# LINK2_LPC4322-USB-BRPWR.net
KiCad netlist of a schematic drawn in Altium Designer
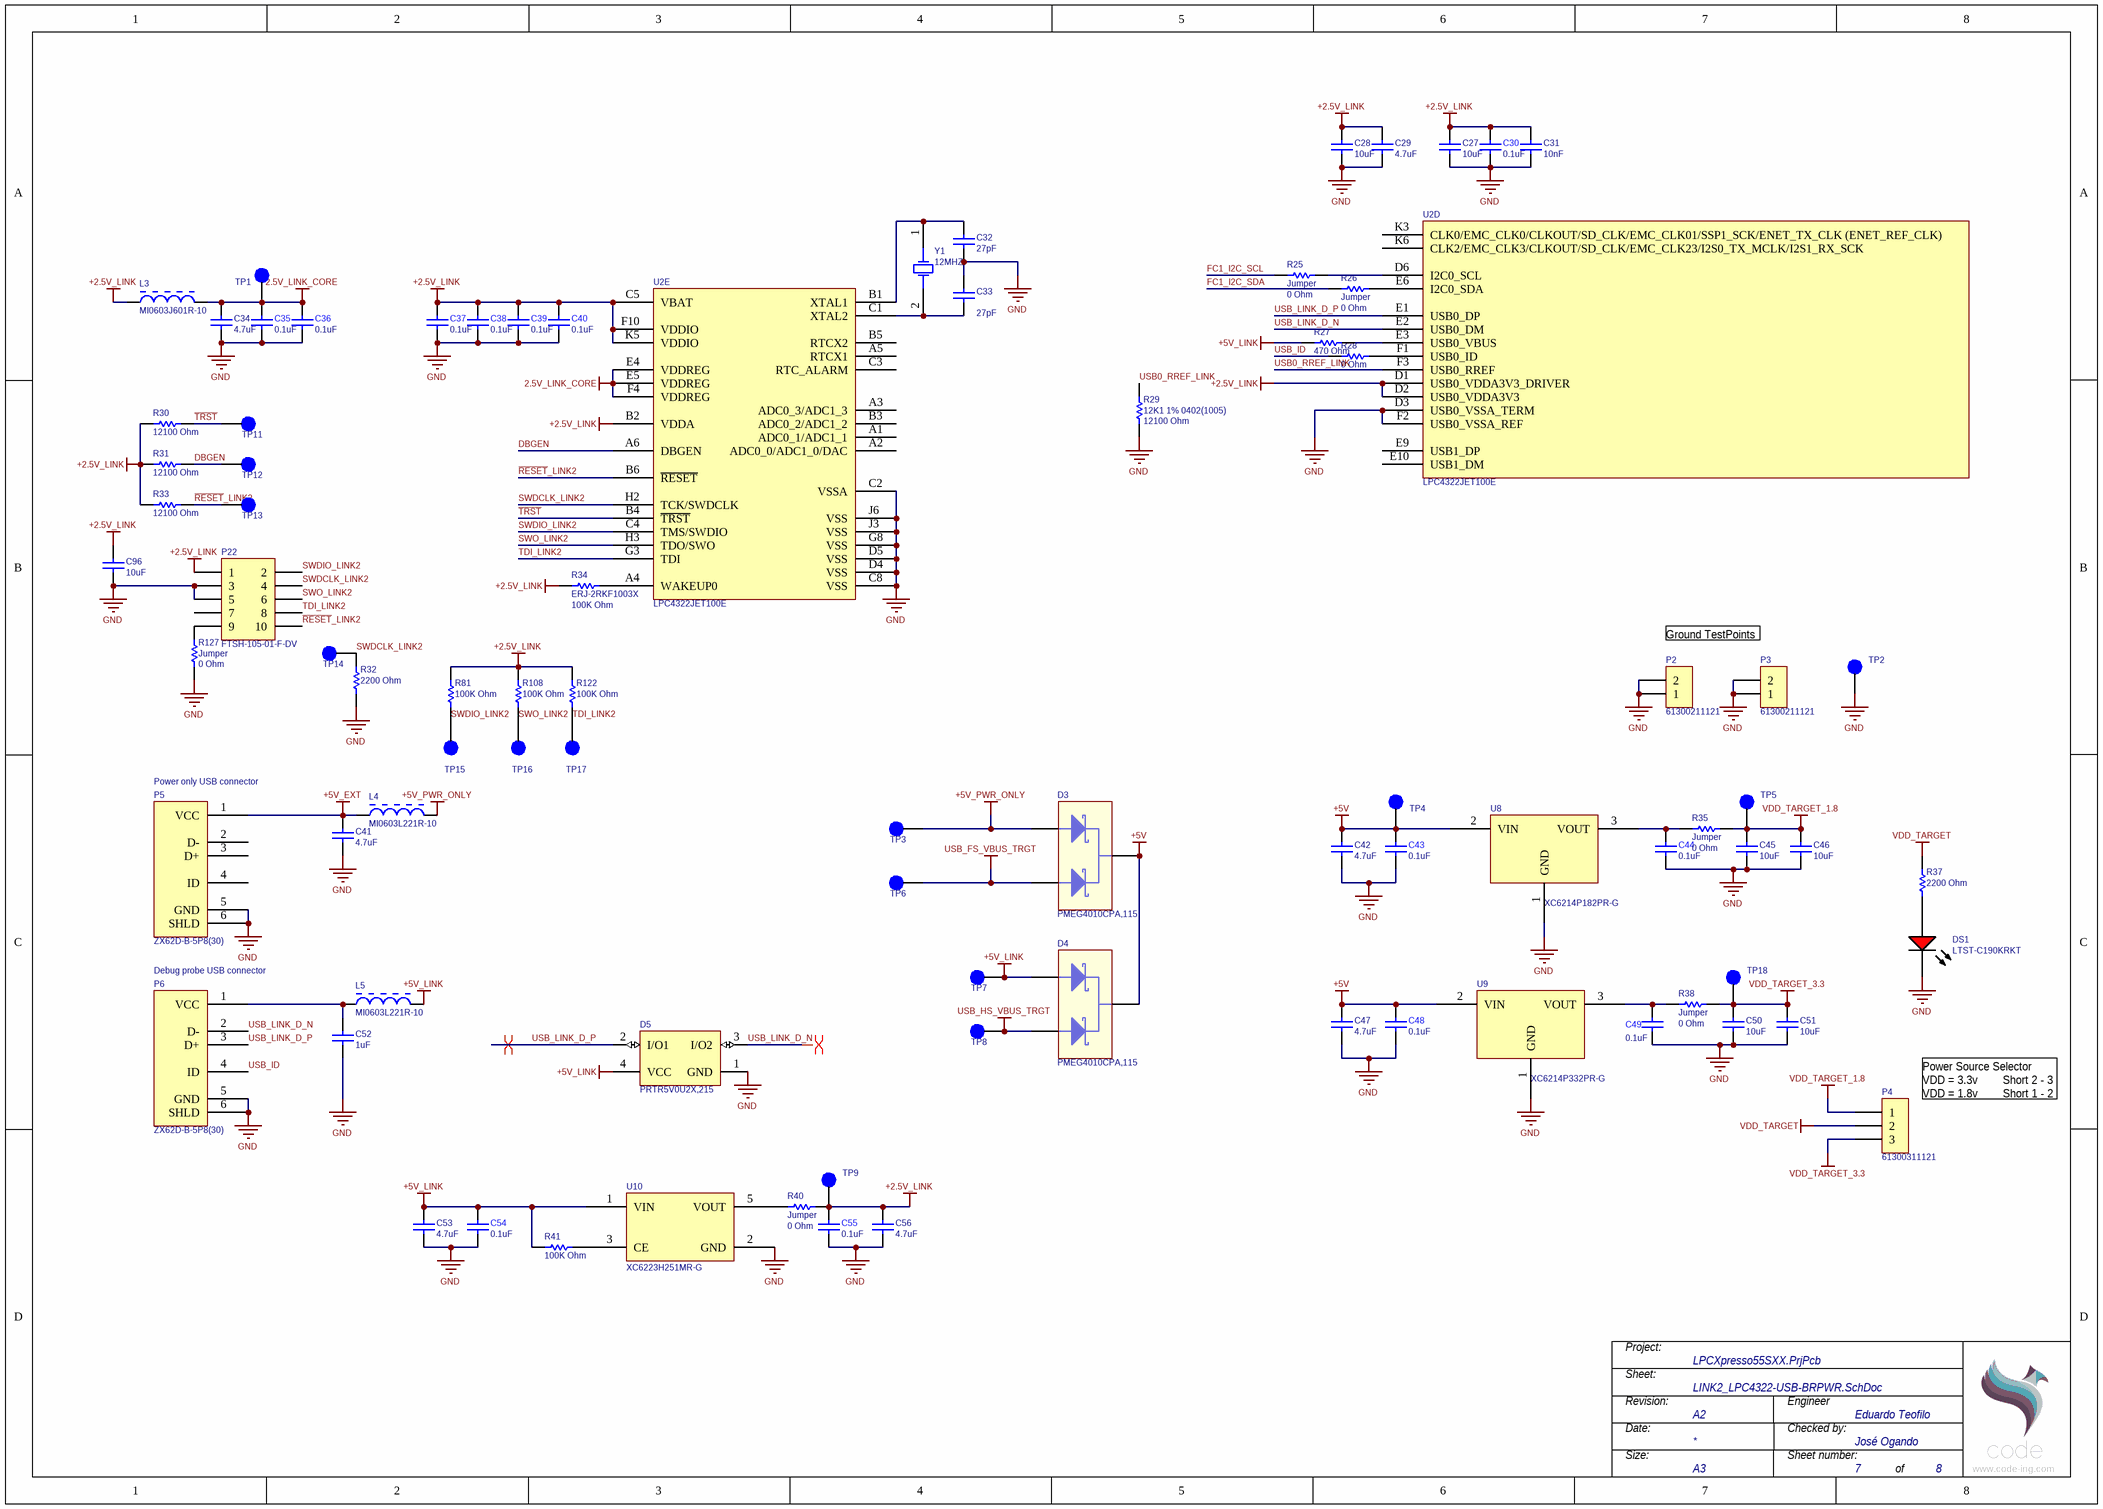
[diagram p0: LINK2_LPC4322-USB-BRPWR.SchDoc]

(export (version "E")
  (design (tool "Eeschema 10.0.6"))
  (components
    (comp (ref "C27")
      (value "10uF")
      (footprint "CAPC0805(2012)145_L")
      (description "CAP 10uF 10V ±10% 0805 (2012 Metric) Thickness 1.45mm SMD")
      (fields (field (name "TOLERANCE") "Â±10%") (field (name "Comment") "CAP 10uF 10V 0805(2012)"))
      (libsource (lib "Altium Content Vault") (part "CMP-1036-04922-1"))
    )
    (comp (ref "C28")
      (value "10uF")
      (footprint "CAPC0805(2012)145_L")
      (description "CAP 10uF 10V ±10% 0805 (2012 Metric) Thickness 1.45mm SMD")
      (fields (field (name "TOLERANCE") "Â±10%") (field (name "Comment") "CAP 10uF 10V 0805(2012)"))
      (libsource (lib "Altium Content Vault") (part "CMP-1036-04922-1"))
    )
    (comp (ref "C29")
      (value "4.7uF")
      (footprint "CAPC0603(1608)100_L")
      (description "CAP 4.7uF 10V ±10% 0603 (1608 Metric) Thickness 1mm SMD")
      (fields (field (name "TOLERANCE") "Â±10%") (field (name "Comment") "CAP 4.7uF 10V 0603(1608)"))
      (libsource (lib "Altium Content Vault") (part "CMP-1035-02785-1"))
    )
    (comp (ref "C30")
      (value "0.1uF")
      (footprint "CAPC1005")
      (description "Capacitor, Yageo, Ceramic, 0.1uF 10% 16V 0402 (1005) X7R")
      (fields
        (field (name "TOLERANCE") "10 %")
        (field (name "Comment") "CC0402KRX7R7BB104")
        (field (name "PUBLISHER") "Altium")
      )
      (libsource (lib "Altium Content Vault") (part "CMP-0001-00074-1"))
    )
    (comp (ref "C31")
      (value "10nF")
      (footprint "CAPC0402(1005)60_L")
      (description "CAP 10nF 25V ±10% 0402 (1005 Metric) Thickness 0.6mm SMD")
      (fields (field (name "TOLERANCE") "Â±10%") (field (name "Comment") "CAP 10nF 25V 0402(1005)"))
      (libsource (lib "Altium Content Vault") (part "CMP-1034-01880-1"))
    )
    (comp (ref "C32")
      (value "27pF")
      (footprint "CAPC0402(1005)60_L")
      (description "CAP 27pF 50V ±5% 0402 (1005 Metric) Thickness 0.6mm SMD")
      (fields (field (name "TOLERANCE") "Â±5%") (field (name "Comment") "CAP 27pF 50V 0402(1005)"))
      (libsource (lib "Altium Content Vault") (part "CMP-1034-00963-1"))
    )
    (comp (ref "C33")
      (value "27pF")
      (footprint "CAPC0402(1005)60_L")
      (description "CAP 27pF 50V ±5% 0402 (1005 Metric) Thickness 0.6mm SMD")
      (fields (field (name "TOLERANCE") "Â±5%") (field (name "Comment") "CAP 27pF 50V 0402(1005)"))
      (libsource (lib "Altium Content Vault") (part "CMP-1034-00963-1"))
    )
    (comp (ref "C34")
      (value "4.7uF")
      (footprint "CAPC0603(1608)100_L")
      (description "CAP 4.7uF 10V ±10% 0603 (1608 Metric) Thickness 1mm SMD")
      (fields (field (name "TOLERANCE") "Â±10%") (field (name "Comment") "CAP 4.7uF 10V 0603(1608)"))
      (libsource (lib "Altium Content Vault") (part "CMP-1035-02785-1"))
    )
    (comp (ref "C35")
      (value "0.1uF")
      (footprint "CAPC1005")
      (description "Capacitor, Yageo, Ceramic, 0.1uF 10% 16V 0402 (1005) X7R")
      (fields
        (field (name "TOLERANCE") "10 %")
        (field (name "Comment") "CC0402KRX7R7BB104")
        (field (name "PUBLISHER") "Altium")
      )
      (libsource (lib "Altium Content Vault") (part "CMP-0001-00074-1"))
    )
    (comp (ref "C36")
      (value "0.1uF")
      (footprint "CAPC1005")
      (description "Capacitor, Yageo, Ceramic, 0.1uF 10% 16V 0402 (1005) X7R")
      (fields
        (field (name "TOLERANCE") "10 %")
        (field (name "Comment") "CC0402KRX7R7BB104")
        (field (name "PUBLISHER") "Altium")
      )
      (libsource (lib "Altium Content Vault") (part "CMP-0001-00074-1"))
    )
    (comp (ref "C37")
      (value "0.1uF")
      (footprint "CAPC1005")
      (description "Capacitor, Yageo, Ceramic, 0.1uF 10% 16V 0402 (1005) X7R")
      (fields
        (field (name "TOLERANCE") "10 %")
        (field (name "Comment") "CC0402KRX7R7BB104")
        (field (name "PUBLISHER") "Altium")
      )
      (libsource (lib "Altium Content Vault") (part "CMP-0001-00074-1"))
    )
    (comp (ref "C38")
      (value "0.1uF")
      (footprint "CAPC1005")
      (description "Capacitor, Yageo, Ceramic, 0.1uF 10% 16V 0402 (1005) X7R")
      (fields
        (field (name "TOLERANCE") "10 %")
        (field (name "Comment") "CC0402KRX7R7BB104")
        (field (name "PUBLISHER") "Altium")
      )
      (libsource (lib "Altium Content Vault") (part "CMP-0001-00074-1"))
    )
    (comp (ref "C39")
      (value "0.1uF")
      (footprint "CAPC1005")
      (description "Capacitor, Yageo, Ceramic, 0.1uF 10% 16V 0402 (1005) X7R")
      (fields
        (field (name "TOLERANCE") "10 %")
        (field (name "Comment") "CC0402KRX7R7BB104")
        (field (name "PUBLISHER") "Altium")
      )
      (libsource (lib "Altium Content Vault") (part "CMP-0001-00074-1"))
    )
    (comp (ref "C40")
      (value "0.1uF")
      (footprint "CAPC1005")
      (description "Capacitor, Yageo, Ceramic, 0.1uF 10% 16V 0402 (1005) X7R")
      (fields
        (field (name "TOLERANCE") "10 %")
        (field (name "Comment") "CC0402KRX7R7BB104")
        (field (name "PUBLISHER") "Altium")
      )
      (libsource (lib "Altium Content Vault") (part "CMP-0001-00074-1"))
    )
    (comp (ref "C41")
      (value "4.7uF")
      (footprint "CAPC0603(1608)100_L")
      (description "CAP 4.7uF 10V ±10% 0603 (1608 Metric) Thickness 1mm SMD")
      (fields (field (name "TOLERANCE") "Â±10%") (field (name "Comment") "CAP 4.7uF 10V 0603(1608)"))
      (libsource (lib "Altium Content Vault") (part "CMP-1035-02785-1"))
    )
    (comp (ref "C42")
      (value "4.7uF")
      (footprint "CAPC0603(1608)100_L")
      (description "CAP 4.7uF 10V ±10% 0603 (1608 Metric) Thickness 1mm SMD")
      (fields (field (name "TOLERANCE") "Â±10%") (field (name "Comment") "CAP 4.7uF 10V 0603(1608)"))
      (libsource (lib "Altium Content Vault") (part "CMP-1035-02785-1"))
    )
    (comp (ref "C43")
      (value "0.1uF")
      (footprint "CAPC1005")
      (description "Capacitor, Yageo, Ceramic, 0.1uF 10% 16V 0402 (1005) X7R")
      (fields
        (field (name "TOLERANCE") "10 %")
        (field (name "Comment") "CC0402KRX7R7BB104")
        (field (name "PUBLISHER") "Altium")
      )
      (libsource (lib "Altium Content Vault") (part "CMP-0001-00074-1"))
    )
    (comp (ref "C44")
      (value "0.1uF")
      (footprint "CAPC1005")
      (description "Capacitor, Yageo, Ceramic, 0.1uF 10% 16V 0402 (1005) X7R")
      (fields
        (field (name "TOLERANCE") "10 %")
        (field (name "Comment") "CC0402KRX7R7BB104")
        (field (name "PUBLISHER") "Altium")
      )
      (libsource (lib "Altium Content Vault") (part "CMP-0001-00074-1"))
    )
    (comp (ref "C45")
      (value "10uF")
      (footprint "CAPC0805(2012)145_L")
      (description "CAP 10uF 10V ±10% 0805 (2012 Metric) Thickness 1.45mm SMD")
      (fields (field (name "TOLERANCE") "Â±10%") (field (name "Comment") "CAP 10uF 10V 0805(2012)"))
      (libsource (lib "Altium Content Vault") (part "CMP-1036-04922-1"))
    )
    (comp (ref "C46")
      (value "10uF")
      (footprint "CAPC0805(2012)145_L")
      (description "CAP 10uF 10V ±10% 0805 (2012 Metric) Thickness 1.45mm SMD")
      (fields (field (name "TOLERANCE") "Â±10%") (field (name "Comment") "CAP 10uF 10V 0805(2012)"))
      (libsource (lib "Altium Content Vault") (part "CMP-1036-04922-1"))
    )
    (comp (ref "C47")
      (value "4.7uF")
      (footprint "CAPC0603(1608)100_L")
      (description "CAP 4.7uF 10V ±10% 0603 (1608 Metric) Thickness 1mm SMD")
      (fields (field (name "TOLERANCE") "Â±10%") (field (name "Comment") "CAP 4.7uF 10V 0603(1608)"))
      (libsource (lib "Altium Content Vault") (part "CMP-1035-02785-1"))
    )
    (comp (ref "C48")
      (value "0.1uF")
      (footprint "CAPC1005")
      (description "Capacitor, Yageo, Ceramic, 0.1uF 10% 16V 0402 (1005) X7R")
      (fields
        (field (name "TOLERANCE") "10 %")
        (field (name "Comment") "CC0402KRX7R7BB104")
        (field (name "PUBLISHER") "Altium")
      )
      (libsource (lib "Altium Content Vault") (part "CMP-0001-00074-1"))
    )
    (comp (ref "C49")
      (value "0.1uF")
      (footprint "CAPC1005")
      (description "Capacitor, Yageo, Ceramic, 0.1uF 10% 16V 0402 (1005) X7R")
      (fields
        (field (name "TOLERANCE") "10 %")
        (field (name "Comment") "CC0402KRX7R7BB104")
        (field (name "PUBLISHER") "Altium")
      )
      (libsource (lib "Altium Content Vault") (part "CMP-0001-00074-1"))
    )
    (comp (ref "C50")
      (value "10uF")
      (footprint "CAPC0805(2012)145_L")
      (description "CAP 10uF 10V ±10% 0805 (2012 Metric) Thickness 1.45mm SMD")
      (fields (field (name "TOLERANCE") "Â±10%") (field (name "Comment") "CAP 10uF 10V 0805(2012)"))
      (libsource (lib "Altium Content Vault") (part "CMP-1036-04922-1"))
    )
    (comp (ref "C51")
      (value "10uF")
      (footprint "CAPC0805(2012)145_L")
      (description "CAP 10uF 10V ±10% 0805 (2012 Metric) Thickness 1.45mm SMD")
      (fields (field (name "TOLERANCE") "Â±10%") (field (name "Comment") "CAP 10uF 10V 0805(2012)"))
      (libsource (lib "Altium Content Vault") (part "CMP-1036-04922-1"))
    )
    (comp (ref "C52")
      (value "1uF")
      (footprint "CAPC0402(1005)60_L")
      (description "CAP 1uF 10V -20% to +80% 0402 (1005 Metric) Thickness 0.6mm SMD")
      (fields (field (name "TOLERANCE") "-20% to +80%") (field (name "Comment") "CAP 1uF 10V 0402(1005)"))
      (libsource (lib "Altium Content Vault") (part "CMP-1034-02118-1"))
    )
    (comp (ref "C53")
      (value "4.7uF")
      (footprint "CAPC0603(1608)100_L")
      (description "CAP 4.7uF 10V ±10% 0603 (1608 Metric) Thickness 1mm SMD")
      (fields (field (name "TOLERANCE") "Â±10%") (field (name "Comment") "CAP 4.7uF 10V 0603(1608)"))
      (libsource (lib "Altium Content Vault") (part "CMP-1035-02785-1"))
    )
    (comp (ref "C54")
      (value "0.1uF")
      (footprint "CAPC1005")
      (description "Capacitor, Yageo, Ceramic, 0.1uF 10% 16V 0402 (1005) X7R")
      (fields
        (field (name "TOLERANCE") "10 %")
        (field (name "Comment") "CC0402KRX7R7BB104")
        (field (name "PUBLISHER") "Altium")
      )
      (libsource (lib "Altium Content Vault") (part "CMP-0001-00074-1"))
    )
    (comp (ref "C55")
      (value "0.1uF")
      (footprint "CAPC1005")
      (description "Capacitor, Yageo, Ceramic, 0.1uF 10% 16V 0402 (1005) X7R")
      (fields
        (field (name "TOLERANCE") "10 %")
        (field (name "Comment") "CC0402KRX7R7BB104")
        (field (name "PUBLISHER") "Altium")
      )
      (libsource (lib "Altium Content Vault") (part "CMP-0001-00074-1"))
    )
    (comp (ref "C56")
      (value "4.7uF")
      (footprint "CAPC0603(1608)100_L")
      (description "CAP 4.7uF 10V ±10% 0603 (1608 Metric) Thickness 1mm SMD")
      (fields (field (name "TOLERANCE") "Â±10%") (field (name "Comment") "CAP 4.7uF 10V 0603(1608)"))
      (libsource (lib "Altium Content Vault") (part "CMP-1035-02785-1"))
    )
    (comp (ref "C96")
      (value "10uF")
      (footprint "CAPC0805(2012)145_L")
      (description "CAP 10uF 10V ±10% 0805 (2012 Metric) Thickness 1.45mm SMD")
      (fields (field (name "TOLERANCE") "Â±10%") (field (name "Comment") "CAP 10uF 10V 0805(2012)"))
      (libsource (lib "Altium Content Vault") (part "CMP-1036-04922-1"))
    )
    (comp (ref "D3")
      (value "PMEG4010CPA,115")
      (footprint "SOT1061")
      (description "DIODE ARRAY SCHOTTKY 40V 3HUSON")
      (fields
        (field (name "MANUFACTURER") "Nexperia USA Inc.")
        (field (name "CREATED BY") "eteoflo")
        (field (name "MODIFIED BY") "*")
      )
      (libsource (lib "Diodes, Rectifiers - Arrays") (part "PMEG4010CPA,115"))
    )
    (comp (ref "D4")
      (value "PMEG4010CPA,115")
      (footprint "SOT1061")
      (description "DIODE ARRAY SCHOTTKY 40V 3HUSON")
      (fields
        (field (name "MANUFACTURER") "Nexperia USA Inc.")
        (field (name "CREATED BY") "eteoflo")
        (field (name "MODIFIED BY") "*")
      )
      (libsource (lib "Diodes, Rectifiers - Arrays") (part "PMEG4010CPA,115"))
    )
    (comp (ref "D5")
      (value "PRTR5V0U2X,215")
      (footprint "NXP-SOT143B-4_V")
      (fields (field (name "MANUFACTURER") "NXP Semiconductors"))
      (libsource (lib "Altium Content Vault") (part "NXP-PRTR5V0U2X,215-4"))
    )
    (comp (ref "DS1")
      (value "LTST-C190KRKT")
      (footprint "LTST-C191KRKT_V")
      (description "LED Uni-Color Red, 62.5 mW, 5 V, -30 to 85 degC, 2-Pin SMD, RoHS, Tape and Reel")
      (fields (field (name "TOLERANCE") "20%"))
      (libsource (lib "Altium Content Vault") (part "LED-RED-AK-2"))
    )
    (comp (ref "L3")
      (value "MI0603J601R-10")
      (footprint "LIRD-MI0603J601R-10_V")
      (description "Ferrite Bead, 600 Ohm, 1 A, -40 to 125 degC, 2-Pin SMD, RoHS, Tape and Reel")
      (fields (field (name "MANUFACTURER") "Laird"))
      (libsource (lib "Altium Content Vault") (part "IND-FB-2"))
    )
    (comp (ref "L4")
      (value "MI0603L221R-10")
      (footprint "LIRD-HZ0603C601R-10-2_V")
      (description "Chip Bead, 100 MHz, 2 A, -40 to 125 degC, 2-Pin SMD (0603), RoHS, Tape and Reel")
      (fields (field (name "MANUFACTURER") "LairdTechnologies"))
      (libsource (lib "Altium Content Vault") (part "IND-FB-2"))
    )
    (comp (ref "L5")
      (value "MI0603L221R-10")
      (footprint "LIRD-HZ0603C601R-10-2_V")
      (description "Chip Bead, 100 MHz, 2 A, -40 to 125 degC, 2-Pin SMD (0603), RoHS, Tape and Reel")
      (fields (field (name "MANUFACTURER") "LairdTechnologies"))
      (libsource (lib "Altium Content Vault") (part "IND-FB-2"))
    )
    (comp (ref "P2")
      (value "61300211121")
      (footprint "61300211121")
      (description "HEADER 2POS SNGL T/H 2.54MM")
      (fields
        (field (name "MANUFACTURER") "Wurth Electronics Inc")
        (field (name "MODIFIED BY") "*")
        (field (name "CREATED BY") "gmoreno")
      )
      (libsource (lib "Rectangular - Headers, Male Pins") (part "61300211121"))
    )
    (comp (ref "P3")
      (value "61300211121")
      (footprint "61300211121")
      (description "HEADER 2POS SNGL T/H 2.54MM")
      (fields
        (field (name "MANUFACTURER") "Wurth Electronics Inc")
        (field (name "MODIFIED BY") "*")
        (field (name "CREATED BY") "gmoreno")
      )
      (libsource (lib "Rectangular - Headers, Male Pins") (part "61300211121"))
    )
    (comp (ref "P4")
      (value "61300311121")
      (footprint "61300311121")
      (description "HEADER 3POS SNGL T/H 2.54MM")
      (fields
        (field (name "MANUFACTURER") "Wurth Electronics Inc")
        (field (name "MODIFIED BY") "*")
        (field (name "CREATED BY") "gmoreno")
      )
      (libsource (lib "Rectangular - Headers, Male Pins") (part "61300311121"))
    )
    (comp (ref "P5")
      (value "ZX62D-B-5P8(30)")
      (footprint "ZX62D-B-5P8(30)")
      (description "CONN RCPT USB MICRO B SMD")
      (fields
        (field (name "MANUFACTURER") "Hirose Electric Co Ltd")
        (field (name "CREATED BY") "eteofilo")
        (field (name "MODIFIED BY") "*")
      )
      (libsource (lib "USB, DVI, HDMI Connectors") (part "ZX62D-B-5P8(30)"))
    )
    (comp (ref "P6")
      (value "ZX62D-B-5P8(30)")
      (footprint "ZX62D-B-5P8(30)")
      (description "CONN RCPT USB MICRO B SMD")
      (fields
        (field (name "MANUFACTURER") "Hirose Electric Co Ltd")
        (field (name "CREATED BY") "eteofilo")
        (field (name "MODIFIED BY") "*")
      )
      (libsource (lib "USB, DVI, HDMI Connectors") (part "ZX62D-B-5P8(30)"))
    )
    (comp (ref "P22")
      (value "FTSH-105-01-F-DV")
      (footprint "FTSH-105-01-L-DV-K")
      (description "CONN HEADER 10POS DUAL .05\" SMD")
      (fields
        (field (name "MANUFACTURER") "Samtec Inc")
        (field (name "CREATED BY") "gmoreno")
        (field (name "MODIFIED BY") "*")
      )
      (libsource (lib "Rectangular - Headers, Male Pins") (part "FTSH-105-01-F-DV"))
    )
    (comp (ref "R25")
      (value "Jumper")
      (footprint "RESC0402(1005)_L")
      (description "Jumper 0402 (1005 Metric)")
      (fields (field (name "TOLERANCE") "None") (field (name "ALTIUM_VALUE") "0 Ohm"))
      (libsource (lib "Altium Content Vault") (part "CMP-1011-00001-1"))
    )
    (comp (ref "R26")
      (value "Jumper")
      (footprint "RESC0402(1005)_L")
      (description "Jumper 0402 (1005 Metric)")
      (fields (field (name "TOLERANCE") "None") (field (name "ALTIUM_VALUE") "0 Ohm"))
      (libsource (lib "Altium Content Vault") (part "CMP-1011-00001-1"))
    )
    (comp (ref "R27")
      (value "470 Ohm")
      (footprint "RESC0402(1005)_L")
      (description "470R 0.063W 5% 0402 (1005 Metric)  SMD")
      (fields (field (name "TOLERANCE") "5 %") (field (name "POWER") "0.063 W"))
      (libsource (lib "Altium Content Vault") (part "CMP-1011-00066-1"))
    )
    (comp (ref "R28")
      (value "0 Ohm")
      (footprint "RESC0402(1005)_L")
      (description "Jumper 0402 (1005 Metric)")
      (fields (field (name "TOLERANCE") "None") (field (name "Comment") "Jumper 0402(1005)"))
      (libsource (lib "Altium Content Vault") (part "CMP-1011-00001-1"))
    )
    (comp (ref "R29")
      (value "12K1 1% 0402(1005)")
      (footprint "RESC0402(1005)_L")
      (description "12K1 0.063W 1% 0402 (1005 Metric)  SMD")
      (fields
        (field (name "ALTIUM_VALUE") "12100 Ohm")
        (field (name "POWER") "0.063 W")
        (field (name "TOLERANCE") "1 %")
      )
      (libsource (lib "Altium Content Vault") (part "CMP-1011-00632-1"))
    )
    (comp (ref "R30")
      (value "12100 Ohm")
      (footprint "RESC0402(1005)_L")
      (description "12K1 0.063W 1% 0402 (1005 Metric)  SMD")
      (fields (field (name "POWER") "0.063 W") (field (name "TOLERANCE") "1 %"))
      (libsource (lib "Altium Content Vault") (part "CMP-1011-00632-1"))
    )
    (comp (ref "R31")
      (value "12100 Ohm")
      (footprint "RESC0402(1005)_L")
      (description "12K1 0.063W 1% 0402 (1005 Metric)  SMD")
      (fields (field (name "POWER") "0.063 W") (field (name "TOLERANCE") "1 %"))
      (libsource (lib "Altium Content Vault") (part "CMP-1011-00632-1"))
    )
    (comp (ref "R32")
      (value "2200 Ohm")
      (footprint "RESC0402(1005)_L")
      (description "2K2 0.063W 1% 0402 (1005 Metric)  SMD")
      (fields (field (name "POWER") "0.063 W") (field (name "TOLERANCE") "1 %"))
      (libsource (lib "Altium Content Vault") (part "CMP-1011-00546-1"))
    )
    (comp (ref "R33")
      (value "12100 Ohm")
      (footprint "RESC0402(1005)_L")
      (description "12K1 0.063W 1% 0402 (1005 Metric)  SMD")
      (fields (field (name "POWER") "0.063 W") (field (name "TOLERANCE") "1 %"))
      (libsource (lib "Altium Content Vault") (part "CMP-1011-00632-1"))
    )
    (comp (ref "R34")
      (value "ERJ-2RKF1003X")
      (footprint "RESC1005X40X25LL05T05")
      (description "Chip Resistor, 100 KOhm, +/- 1%, 100 mW, -55 to 155 degC, 0402 (1005 Metric), RoHS, Tape and Reel")
      (fields
        (field (name "TOLERANCE") "1%")
        (field (name "MANUFACTURER") "Basic Passives")
        (field (name "ALTIUM_VALUE") "100K Ohm")
      )
      (libsource (lib "Altium Content Vault") (part "RES-2"))
    )
    (comp (ref "R35")
      (value "Jumper")
      (footprint "RESC0402(1005)_L")
      (description "Jumper 0402 (1005 Metric)")
      (fields (field (name "TOLERANCE") "None") (field (name "ALTIUM_VALUE") "0 Ohm"))
      (libsource (lib "Altium Content Vault") (part "CMP-1011-00001-1"))
    )
    (comp (ref "R37")
      (value "2200 Ohm")
      (footprint "RESC0402(1005)_L")
      (description "2K2 0.063W 1% 0402 (1005 Metric)  SMD")
      (fields (field (name "POWER") "0.063 W") (field (name "TOLERANCE") "1 %"))
      (libsource (lib "Altium Content Vault") (part "CMP-1011-00546-1"))
    )
    (comp (ref "R38")
      (value "Jumper")
      (footprint "RESC0402(1005)_L")
      (description "Jumper 0402 (1005 Metric)")
      (fields (field (name "TOLERANCE") "None") (field (name "ALTIUM_VALUE") "0 Ohm"))
      (libsource (lib "Altium Content Vault") (part "CMP-1011-00001-1"))
    )
    (comp (ref "R40")
      (value "Jumper")
      (footprint "RESC0402(1005)_L")
      (description "Jumper 0402 (1005 Metric)")
      (fields (field (name "TOLERANCE") "None") (field (name "ALTIUM_VALUE") "0 Ohm"))
      (libsource (lib "Altium Content Vault") (part "CMP-1011-00001-1"))
    )
    (comp (ref "R41")
      (value "100K Ohm")
      (footprint "RESC1005X40X25LL05T05")
      (description "Chip Resistor, 100 KOhm, +/- 1%, 100 mW, -55 to 155 degC, 0402 (1005 Metric), RoHS, Tape and Reel")
      (fields (field (name "TOLERANCE") "1%") (field (name "MANUFACTURER") "Basic Passives"))
      (libsource (lib "Altium Content Vault") (part "CMP-2002-00608-3"))
    )
    (comp (ref "R81")
      (value "100K Ohm")
      (footprint "RESC1005X40X25LL05T05")
      (description "Chip Resistor, 100 KOhm, +/- 1%, 100 mW, -55 to 155 degC, 0402 (1005 Metric), RoHS, Tape and Reel")
      (fields (field (name "TOLERANCE") "1%") (field (name "MANUFACTURER") "Basic Passives"))
      (libsource (lib "Altium Content Vault") (part "CMP-2002-00608-3"))
    )
    (comp (ref "R108")
      (value "100K Ohm")
      (footprint "RESC1005X40X25LL05T05")
      (description "Chip Resistor, 100 KOhm, +/- 1%, 100 mW, -55 to 155 degC, 0402 (1005 Metric), RoHS, Tape and Reel")
      (fields (field (name "TOLERANCE") "1%") (field (name "MANUFACTURER") "Basic Passives"))
      (libsource (lib "Altium Content Vault") (part "CMP-2002-00608-3"))
    )
    (comp (ref "R122")
      (value "100K Ohm")
      (footprint "RESC1005X40X25LL05T05")
      (description "Chip Resistor, 100 KOhm, +/- 1%, 100 mW, -55 to 155 degC, 0402 (1005 Metric), RoHS, Tape and Reel")
      (fields (field (name "TOLERANCE") "1%") (field (name "MANUFACTURER") "Basic Passives"))
      (libsource (lib "Altium Content Vault") (part "CMP-2002-00608-3"))
    )
    (comp (ref "R127")
      (value "Jumper")
      (footprint "RESC0402(1005)_L")
      (description "Jumper 0402 (1005 Metric)")
      (fields (field (name "TOLERANCE") "None") (field (name "ALTIUM_VALUE") "0 Ohm"))
      (libsource (lib "Altium Content Vault") (part "CMP-1011-00001-1"))
    )
    (comp (ref "TP1")
      (value "TP 1mm")
      (footprint "SMT Test Point")
      (description "PCB TEST POINT SMT 1mm")
      (fields (field (name "MODIFIED BY") "*") (field (name "CREATED BY") "gmoreno"))
      (libsource (lib "") (part "TP 1mm_1"))
    )
    (comp (ref "TP2")
      (value "TP 1mm")
      (footprint "SMT Test Point")
      (description "PCB TEST POINT SMT 1mm")
      (fields (field (name "MODIFIED BY") "*") (field (name "CREATED BY") "gmoreno"))
      (libsource (lib "") (part "TP 1mm_1"))
    )
    (comp (ref "TP3")
      (value "TP 1mm")
      (footprint "SMT Test Point")
      (description "PCB TEST POINT SMT 1mm")
      (fields (field (name "MODIFIED BY") "*") (field (name "CREATED BY") "gmoreno"))
      (libsource (lib "PCB Test Points") (part "TP 1mm"))
    )
    (comp (ref "TP4")
      (value "TP 1mm")
      (footprint "SMT Test Point")
      (description "PCB TEST POINT SMT 1mm")
      (fields (field (name "MODIFIED BY") "*") (field (name "CREATED BY") "gmoreno"))
      (libsource (lib "") (part "TP 1mm_1"))
    )
    (comp (ref "TP5")
      (value "TP 1mm")
      (footprint "SMT Test Point")
      (description "PCB TEST POINT SMT 1mm")
      (fields (field (name "MODIFIED BY") "*") (field (name "CREATED BY") "gmoreno"))
      (libsource (lib "") (part "TP 1mm_1"))
    )
    (comp (ref "TP6")
      (value "TP 1mm")
      (footprint "SMT Test Point")
      (description "PCB TEST POINT SMT 1mm")
      (fields (field (name "MODIFIED BY") "*") (field (name "CREATED BY") "gmoreno"))
      (libsource (lib "PCB Test Points") (part "TP 1mm"))
    )
    (comp (ref "TP7")
      (value "TP 1mm")
      (footprint "SMT Test Point")
      (description "PCB TEST POINT SMT 1mm")
      (fields (field (name "MODIFIED BY") "*") (field (name "CREATED BY") "gmoreno"))
      (libsource (lib "PCB Test Points") (part "TP 1mm"))
    )
    (comp (ref "TP8")
      (value "TP 1mm")
      (footprint "SMT Test Point")
      (description "PCB TEST POINT SMT 1mm")
      (fields (field (name "MODIFIED BY") "*") (field (name "CREATED BY") "gmoreno"))
      (libsource (lib "PCB Test Points") (part "TP 1mm"))
    )
    (comp (ref "TP9")
      (value "TP 1mm")
      (footprint "SMT Test Point")
      (description "PCB TEST POINT SMT 1mm")
      (fields (field (name "MODIFIED BY") "*") (field (name "CREATED BY") "gmoreno"))
      (libsource (lib "") (part "TP 1mm_1"))
    )
    (comp (ref "TP11")
      (value "TPAD 0.8mm")
      (footprint "TH Test Pad 0.8mm")
      (description "PCB TEST PAD TH 0.8mm")
      (fields (field (name "MODIFIED BY") "*") (field (name "CREATED BY") "eteofilo"))
      (libsource (lib "") (part "TP 0.8mm_1"))
    )
    (comp (ref "TP12")
      (value "TPAD 0.8mm")
      (footprint "TH Test Pad 0.8mm")
      (description "PCB TEST PAD TH 0.8mm")
      (fields (field (name "MODIFIED BY") "*") (field (name "CREATED BY") "eteofilo"))
      (libsource (lib "") (part "TP 0.8mm_1"))
    )
    (comp (ref "TP13")
      (value "TPAD 0.8mm")
      (footprint "TH Test Pad 0.8mm")
      (description "PCB TEST PAD TH 0.8mm")
      (fields (field (name "MODIFIED BY") "*") (field (name "CREATED BY") "eteofilo"))
      (libsource (lib "") (part "TP 0.8mm_1"))
    )
    (comp (ref "TP14")
      (value "TPAD 0.8mm")
      (footprint "TH Test Pad 0.8mm")
      (description "PCB TEST PAD TH 0.8mm")
      (fields (field (name "MODIFIED BY") "*") (field (name "CREATED BY") "eteofilo"))
      (libsource (lib "") (part "TP 0.8mm_2"))
    )
    (comp (ref "TP15")
      (value "TPAD 0.8mm")
      (footprint "TH Test Pad 0.8mm")
      (description "PCB TEST PAD TH 0.8mm")
      (fields (field (name "MODIFIED BY") "*") (field (name "CREATED BY") "eteofilo"))
      (libsource (lib "PCB Test Points") (part "TP 0.8mm"))
    )
    (comp (ref "TP16")
      (value "TPAD 0.8mm")
      (footprint "TH Test Pad 0.8mm")
      (description "PCB TEST PAD TH 0.8mm")
      (fields (field (name "MODIFIED BY") "*") (field (name "CREATED BY") "eteofilo"))
      (libsource (lib "PCB Test Points") (part "TP 0.8mm"))
    )
    (comp (ref "TP17")
      (value "TPAD 0.8mm")
      (footprint "TH Test Pad 0.8mm")
      (description "PCB TEST PAD TH 0.8mm")
      (fields (field (name "MODIFIED BY") "*") (field (name "CREATED BY") "eteofilo"))
      (libsource (lib "PCB Test Points") (part "TP 0.8mm"))
    )
    (comp (ref "TP18")
      (value "TP 1mm")
      (footprint "SMT Test Point")
      (description "PCB TEST POINT SMT 1mm")
      (fields (field (name "MODIFIED BY") "*") (field (name "CREATED BY") "gmoreno"))
      (libsource (lib "") (part "TP 1mm_1"))
    )
    (comp (ref "U2")
      (value "LPC4322JET100E")
      (footprint "BGA100_9x9x1.2mm")
      (description "IC MCU 32BIT 512KB FLASH 100BGA")
      (fields
        (field (name "MANUFACTURER") "NXP")
        (field (name "CREATED BY") "eteofilo")
        (field (name "MODIFIED BY") "*")
      )
      (libsource (lib "Embedded - Microcontrollers") (part "LPC4322JET100E"))
    )
    (comp (ref "U8")
      (value "XC6214P182PR-G")
      (footprint "SOT-89-3")
      (description "IC REG LDO 1.8V 0.5A SOT89-3")
      (fields
        (field (name "MANUFACTURER") "Torex Semiconductor Ltd")
        (field (name "CREATED BY") "eteofilo")
        (field (name "MODIFIED BY") "*")
      )
      (libsource (lib "PMIC - Voltage Regulators - Linear (LDO)") (part "XC6214P182PR-G"))
    )
    (comp (ref "U9")
      (value "XC6214P332PR-G")
      (footprint "SOT-89-3")
      (description "IC REG LDO 3.3V 0.5A SOT89-3")
      (fields
        (field (name "MANUFACTURER") "Torex Semiconductor Ltd")
        (field (name "CREATED BY") "eteofilo")
        (field (name "MODIFIED BY") "*")
      )
      (libsource (lib "PMIC - Voltage Regulators - Linear (LDO)") (part "XC6214P332PR-G"))
    )
    (comp (ref "U10")
      (value "XC6223H251MR-G")
      (footprint "SOT25")
      (description "IC REG LINEAR 2.5V SOT25-5")
      (fields
        (field (name "MANUFACTURER") "Torex Semiconductor")
        (field (name "MODIFIED BY") "*")
        (field (name "CREATED BY") "eteofilo")
      )
      (libsource (lib "PMIC - Voltage Regulators - Linear (LDO)") (part "XC6223H251MR-G"))
    )
    (comp (ref "Y1")
      (value "12MHZ")
      (footprint "2-LEAD 11.4X4.8")
      (description "CRYSTAL 12.0000MHZ 18PF SMD")
      (fields
        (field (name "MANUFACTURER PART #") "ABLS2-12.000MHZ-D4Y-T")
        (field (name "MANUFACTURER") "Abracon LLC")
        (field (name "MODIFIED BY") "*")
        (field (name "CREATED BY") "eteofilo")
      )
      (libsource (lib "Crystals") (part "ABLS2-12.000MHZ-D4Y-T"))
    )
  )
  (nets
    (net (code "1") (name "+2.5V_LINK") (class "Default")
      (node (ref "C27") (pin "2") (pinfunction "2_2") (pintype "passive"))
      (node (ref "C28") (pin "2") (pinfunction "2_2") (pintype "passive"))
      (node (ref "C29") (pin "2") (pinfunction "2_2") (pintype "passive"))
      (node (ref "C30") (pin "1") (pinfunction "1_1") (pintype "passive"))
      (node (ref "C31") (pin "2") (pinfunction "2_2") (pintype "passive"))
      (node (ref "C37") (pin "1") (pinfunction "1_1") (pintype "passive"))
      (node (ref "C38") (pin "1") (pinfunction "1_1") (pintype "passive"))
      (node (ref "C39") (pin "1") (pinfunction "1_1") (pintype "passive"))
      (node (ref "C40") (pin "1") (pinfunction "1_1") (pintype "passive"))
      (node (ref "C55") (pin "1") (pinfunction "1_1") (pintype "passive"))
      (node (ref "C56") (pin "2") (pinfunction "2_2") (pintype "passive"))
      (node (ref "C96") (pin "2") (pinfunction "2_2") (pintype "passive"))
      (node (ref "L3") (pin "1") (pinfunction "1_1") (pintype "passive"))
      (node (ref "P22") (pin "1") (pinfunction "1_1") (pintype "passive"))
      (node (ref "R108") (pin "2") (pinfunction "2_2") (pintype "passive"))
      (node (ref "R122") (pin "2") (pinfunction "2_2") (pintype "passive"))
      (node (ref "R30") (pin "2") (pinfunction "2_2") (pintype "passive"))
      (node (ref "R31") (pin "1") (pinfunction "1_1") (pintype "passive"))
      (node (ref "R33") (pin "2") (pinfunction "2_2") (pintype "passive"))
      (node (ref "R34") (pin "1") (pinfunction "1_1") (pintype "passive"))
      (node (ref "R40") (pin "1") (pinfunction "1_1") (pintype "passive"))
      (node (ref "R81") (pin "2") (pinfunction "2_2") (pintype "passive"))
      (node (ref "TP9") (pin "1") (pinfunction "TP_1") (pintype "passive"))
      (node (ref "U2") (pin "B2") (pinfunction "VDDA_B2") (pintype "passive"))
      (node (ref "U2") (pin "C5") (pinfunction "VBAT_C5") (pintype "passive"))
      (node (ref "U2") (pin "D1") (pinfunction "USB0_VDDA3V3_DRIVER_D1") (pintype "passive"))
      (node (ref "U2") (pin "D2") (pinfunction "USB0_VDDA3V3_D2") (pintype "passive"))
      (node (ref "U2") (pin "F10") (pinfunction "VDDIO_F10") (pintype "passive"))
      (node (ref "U2") (pin "K5") (pinfunction "VDDIO_K5") (pintype "passive"))
    )
    (net (code "2") (name "+5V") (class "Default")
      (node (ref "C42") (pin "2") (pinfunction "2_2") (pintype "passive"))
      (node (ref "C43") (pin "1") (pinfunction "1_1") (pintype "passive"))
      (node (ref "C47") (pin "2") (pinfunction "2_2") (pintype "passive"))
      (node (ref "C48") (pin "1") (pinfunction "1_1") (pintype "passive"))
      (node (ref "D3") (pin "3") (pinfunction "K_3") (pintype "passive"))
      (node (ref "D4") (pin "3") (pinfunction "K_3") (pintype "passive"))
      (node (ref "TP4") (pin "1") (pinfunction "TP_1") (pintype "passive"))
      (node (ref "U8") (pin "2") (pinfunction "VIN_2") (pintype "passive"))
      (node (ref "U9") (pin "2") (pinfunction "VIN_2") (pintype "passive"))
    )
    (net (code "3") (name "+5V_EXT") (class "Default")
      (node (ref "C41") (pin "2") (pinfunction "2_2") (pintype "passive"))
      (node (ref "L4") (pin "1") (pinfunction "1_1") (pintype "passive"))
      (node (ref "P5") (pin "1") (pinfunction "VCC_1") (pintype "passive"))
    )
    (net (code "4") (name "+5V_LINK") (class "Default")
      (node (ref "C53") (pin "2") (pinfunction "2_2") (pintype "passive"))
      (node (ref "C54") (pin "1") (pinfunction "1_1") (pintype "passive"))
      (node (ref "D4") (pin "1") (pinfunction "A1_1") (pintype "passive"))
      (node (ref "D5") (pin "4") (pinfunction "VCC_4") (pintype "power_in"))
      (node (ref "L5") (pin "2") (pinfunction "2_2") (pintype "passive"))
      (node (ref "R27") (pin "2") (pinfunction "2_2") (pintype "passive"))
      (node (ref "R41") (pin "1") (pinfunction "1_1") (pintype "passive"))
      (node (ref "TP7") (pin "1") (pinfunction "TP_1") (pintype "passive"))
      (node (ref "U10") (pin "1") (pinfunction "VIN_1") (pintype "passive"))
    )
    (net (code "5") (name "+5V_PWR_ONLY") (class "Default")
      (node (ref "D3") (pin "1") (pinfunction "A1_1") (pintype "passive"))
      (node (ref "L4") (pin "2") (pinfunction "2_2") (pintype "passive"))
      (node (ref "TP3") (pin "1") (pinfunction "TP_1") (pintype "passive"))
    )
    (net (code "6") (name "/DBGEN") (class "Default")
      (node (ref "R31") (pin "2") (pinfunction "2_2") (pintype "passive"))
      (node (ref "TP12") (pin "1") (pinfunction "TP_1") (pintype "passive"))
      (node (ref "U2") (pin "A6") (pinfunction "DBGEN_A6") (pintype "passive"))
    )
    (net (code "7") (name "/FC1_I2C_SCL") (class "Default")
      (node (ref "R25") (pin "2") (pinfunction "2_2") (pintype "passive"))
    )
    (net (code "8") (name "/FC1_I2C_SDA") (class "Default")
      (node (ref "R26") (pin "2") (pinfunction "2_2") (pintype "passive"))
    )
    (net (code "9") (name "/SWDCLK_LINK2") (class "Default")
      (node (ref "P22") (pin "4") (pinfunction "4_4") (pintype "passive"))
      (node (ref "R32") (pin "2") (pinfunction "2_2") (pintype "passive"))
      (node (ref "TP14") (pin "1") (pinfunction "TP_1") (pintype "passive"))
      (node (ref "U2") (pin "H2") (pinfunction "TCK/SWDCLK_H2") (pintype "passive"))
    )
    (net (code "10") (name "/SWDIO_LINK2") (class "Default")
      (node (ref "P22") (pin "2") (pinfunction "2_2") (pintype "passive"))
      (node (ref "R81") (pin "1") (pinfunction "1_1") (pintype "passive"))
      (node (ref "TP15") (pin "1") (pinfunction "TP_1") (pintype "passive"))
      (node (ref "U2") (pin "C4") (pinfunction "TMS/SWDIO_C4") (pintype "passive"))
    )
    (net (code "11") (name "/SWO_LINK2") (class "Default")
      (node (ref "P22") (pin "6") (pinfunction "6_6") (pintype "passive"))
      (node (ref "R108") (pin "1") (pinfunction "1_1") (pintype "passive"))
      (node (ref "TP16") (pin "1") (pinfunction "TP_1") (pintype "passive"))
      (node (ref "U2") (pin "H3") (pinfunction "TDO/SWO_H3") (pintype "passive"))
    )
    (net (code "12") (name "/TDI_LINK2") (class "Default")
      (node (ref "P22") (pin "8") (pinfunction "8_8") (pintype "passive"))
      (node (ref "R122") (pin "1") (pinfunction "1_1") (pintype "passive"))
      (node (ref "TP17") (pin "1") (pinfunction "TP_1") (pintype "passive"))
      (node (ref "U2") (pin "G3") (pinfunction "TDI_G3") (pintype "passive"))
    )
    (net (code "13") (name "/USB0_RREF_LINK") (class "Default")
      (node (ref "R29") (pin "1") (pinfunction "1_1") (pintype "passive"))
      (node (ref "U2") (pin "F3") (pinfunction "USB0_RREF_F3") (pintype "passive"))
    )
    (net (code "14") (name "/USB_ID") (class "Default")
      (node (ref "P6") (pin "4") (pinfunction "ID_4") (pintype "passive"))
      (node (ref "R28") (pin "1") (pinfunction "1_1") (pintype "passive"))
    )
    (net (code "15") (name "/USB_LINK_D_N") (class "Default")
      (node (ref "D5") (pin "3") (pinfunction "I/O2_3") (pintype "bidirectional"))
      (node (ref "P6") (pin "2") (pinfunction "D-_2") (pintype "passive"))
      (node (ref "U2") (pin "E2") (pinfunction "USB0_DM_E2") (pintype "passive"))
    )
    (net (code "16") (name "/USB_LINK_D_P") (class "Default")
      (node (ref "D5") (pin "2") (pinfunction "I/O1_2") (pintype "bidirectional"))
      (node (ref "P6") (pin "3") (pinfunction "D+_3") (pintype "passive"))
      (node (ref "U2") (pin "E1") (pinfunction "USB0_DP_E1") (pintype "passive"))
    )
    (net (code "17") (name "/~{RESET}_LINK2") (class "Default")
      (node (ref "P22") (pin "10") (pinfunction "10_10") (pintype "passive"))
      (node (ref "R33") (pin "1") (pinfunction "1_1") (pintype "passive"))
      (node (ref "TP13") (pin "1") (pinfunction "TP_1") (pintype "passive"))
      (node (ref "U2") (pin "B6") (pinfunction "~{RESET}_B6") (pintype "passive"))
    )
    (net (code "18") (name "/~{TRST}") (class "Default")
      (node (ref "R30") (pin "1") (pinfunction "1_1") (pintype "passive"))
      (node (ref "TP11") (pin "1") (pinfunction "TP_1") (pintype "passive"))
      (node (ref "U2") (pin "B4") (pinfunction "~{TRST}_B4") (pintype "passive"))
    )
    (net (code "19") (name "2.5V_LINK_CORE") (class "Default")
      (node (ref "C34") (pin "2") (pinfunction "2_2") (pintype "passive"))
      (node (ref "C35") (pin "1") (pinfunction "1_1") (pintype "passive"))
      (node (ref "C36") (pin "1") (pinfunction "1_1") (pintype "passive"))
      (node (ref "L3") (pin "2") (pinfunction "2_2") (pintype "passive"))
      (node (ref "TP1") (pin "1") (pinfunction "TP_1") (pintype "passive"))
      (node (ref "U2") (pin "E4") (pinfunction "VDDREG_E4") (pintype "passive"))
      (node (ref "U2") (pin "E5") (pinfunction "VDDREG_E5") (pintype "passive"))
      (node (ref "U2") (pin "F4") (pinfunction "VDDREG_F4") (pintype "passive"))
    )
    (net (code "20") (name "GND") (class "Default")
      (node (ref "C27") (pin "1") (pinfunction "1_1") (pintype "passive"))
      (node (ref "C28") (pin "1") (pinfunction "1_1") (pintype "passive"))
      (node (ref "C29") (pin "1") (pinfunction "1_1") (pintype "passive"))
      (node (ref "C30") (pin "2") (pinfunction "2_2") (pintype "passive"))
      (node (ref "C31") (pin "1") (pinfunction "1_1") (pintype "passive"))
      (node (ref "C32") (pin "1") (pinfunction "1_1") (pintype "passive"))
      (node (ref "C33") (pin "2") (pinfunction "2_2") (pintype "passive"))
      (node (ref "C34") (pin "1") (pinfunction "1_1") (pintype "passive"))
      (node (ref "C35") (pin "2") (pinfunction "2_2") (pintype "passive"))
      (node (ref "C36") (pin "2") (pinfunction "2_2") (pintype "passive"))
      (node (ref "C37") (pin "2") (pinfunction "2_2") (pintype "passive"))
      (node (ref "C38") (pin "2") (pinfunction "2_2") (pintype "passive"))
      (node (ref "C39") (pin "2") (pinfunction "2_2") (pintype "passive"))
      (node (ref "C40") (pin "2") (pinfunction "2_2") (pintype "passive"))
      (node (ref "C41") (pin "1") (pinfunction "1_1") (pintype "passive"))
      (node (ref "C42") (pin "1") (pinfunction "1_1") (pintype "passive"))
      (node (ref "C43") (pin "2") (pinfunction "2_2") (pintype "passive"))
      (node (ref "C44") (pin "2") (pinfunction "2_2") (pintype "passive"))
      (node (ref "C45") (pin "1") (pinfunction "1_1") (pintype "passive"))
      (node (ref "C46") (pin "1") (pinfunction "1_1") (pintype "passive"))
      (node (ref "C47") (pin "1") (pinfunction "1_1") (pintype "passive"))
      (node (ref "C48") (pin "2") (pinfunction "2_2") (pintype "passive"))
      (node (ref "C49") (pin "2") (pinfunction "2_2") (pintype "passive"))
      (node (ref "C50") (pin "1") (pinfunction "1_1") (pintype "passive"))
      (node (ref "C51") (pin "1") (pinfunction "1_1") (pintype "passive"))
      (node (ref "C52") (pin "1") (pinfunction "1_1") (pintype "passive"))
      (node (ref "C53") (pin "1") (pinfunction "1_1") (pintype "passive"))
      (node (ref "C54") (pin "2") (pinfunction "2_2") (pintype "passive"))
      (node (ref "C55") (pin "2") (pinfunction "2_2") (pintype "passive"))
      (node (ref "C56") (pin "1") (pinfunction "1_1") (pintype "passive"))
      (node (ref "C96") (pin "1") (pinfunction "1_1") (pintype "passive"))
      (node (ref "D5") (pin "1") (pinfunction "GND_1") (pintype "power_in"))
      (node (ref "DS1") (pin "2") (pinfunction "K_2") (pintype "passive"))
      (node (ref "P2") (pin "1") (pinfunction "1_1") (pintype "passive"))
      (node (ref "P2") (pin "2") (pinfunction "2_2") (pintype "passive"))
      (node (ref "P22") (pin "3") (pinfunction "3_3") (pintype "passive"))
      (node (ref "P22") (pin "5") (pinfunction "5_5") (pintype "passive"))
      (node (ref "P3") (pin "1") (pinfunction "1_1") (pintype "passive"))
      (node (ref "P3") (pin "2") (pinfunction "2_2") (pintype "passive"))
      (node (ref "P5") (pin "5") (pinfunction "GND_5") (pintype "passive"))
      (node (ref "P5") (pin "6") (pinfunction "SHLD_6") (pintype "passive"))
      (node (ref "P6") (pin "5") (pinfunction "GND_5") (pintype "passive"))
      (node (ref "P6") (pin "6") (pinfunction "SHLD_6") (pintype "passive"))
      (node (ref "R127") (pin "1") (pinfunction "1_1") (pintype "passive"))
      (node (ref "R29") (pin "2") (pinfunction "2_2") (pintype "passive"))
      (node (ref "R32") (pin "1") (pinfunction "1_1") (pintype "passive"))
      (node (ref "TP2") (pin "1") (pinfunction "TP_1") (pintype "passive"))
      (node (ref "U10") (pin "2") (pinfunction "GND_2") (pintype "passive"))
      (node (ref "U2") (pin "C2") (pinfunction "VSSA_C2") (pintype "passive"))
      (node (ref "U2") (pin "C8") (pinfunction "VSS_C8") (pintype "passive"))
      (node (ref "U2") (pin "D3") (pinfunction "USB0_VSSA_TERM_D3") (pintype "passive"))
      (node (ref "U2") (pin "D4") (pinfunction "VSS_D4") (pintype "passive"))
      (node (ref "U2") (pin "D5") (pinfunction "VSS_D5") (pintype "passive"))
      (node (ref "U2") (pin "F2") (pinfunction "USB0_VSSA_REF_F2") (pintype "passive"))
      (node (ref "U2") (pin "G8") (pinfunction "VSS_G8") (pintype "passive"))
      (node (ref "U2") (pin "J3") (pinfunction "VSS_J3") (pintype "passive"))
      (node (ref "U2") (pin "J6") (pinfunction "VSS_J6") (pintype "passive"))
      (node (ref "U8") (pin "1") (pinfunction "GND_1") (pintype "passive"))
      (node (ref "U9") (pin "1") (pinfunction "GND_1") (pintype "passive"))
    )
    (net (code "21") (name "Net-(DS1-A)") (class "Default")
      (node (ref "DS1") (pin "1") (pinfunction "A_1") (pintype "passive"))
      (node (ref "R37") (pin "1") (pinfunction "1_1") (pintype "passive"))
    )
    (net (code "22") (name "Net-(P6-VCC)") (class "Default")
      (node (ref "C52") (pin "2") (pinfunction "2_2") (pintype "passive"))
      (node (ref "L5") (pin "1") (pinfunction "1_1") (pintype "passive"))
      (node (ref "P6") (pin "1") (pinfunction "VCC_1") (pintype "passive"))
    )
    (net (code "23") (name "Net-(P22-Pad9)") (class "Default")
      (node (ref "P22") (pin "9") (pinfunction "9_9") (pintype "passive"))
      (node (ref "R127") (pin "2") (pinfunction "2_2") (pintype "passive"))
    )
    (net (code "24") (name "Net-(U2D-I2C0_SCL)") (class "Default")
      (node (ref "R25") (pin "1") (pinfunction "1_1") (pintype "passive"))
      (node (ref "U2") (pin "D6") (pinfunction "I2C0_SCL_D6") (pintype "passive"))
    )
    (net (code "25") (name "Net-(U2D-I2C0_SDA)") (class "Default")
      (node (ref "R26") (pin "1") (pinfunction "1_1") (pintype "passive"))
      (node (ref "U2") (pin "E6") (pinfunction "I2C0_SDA_E6") (pintype "passive"))
    )
    (net (code "26") (name "Net-(U2D-USB0_ID)") (class "Default")
      (node (ref "R28") (pin "2") (pinfunction "2_2") (pintype "passive"))
      (node (ref "U2") (pin "F1") (pinfunction "USB0_ID_F1") (pintype "passive"))
    )
    (net (code "27") (name "Net-(U2D-USB0_VBUS)") (class "Default")
      (node (ref "R27") (pin "1") (pinfunction "1_1") (pintype "passive"))
      (node (ref "U2") (pin "E3") (pinfunction "USB0_VBUS_E3") (pintype "passive"))
    )
    (net (code "28") (name "Net-(U2E-WAKEUP0)") (class "Default")
      (node (ref "R34") (pin "2") (pinfunction "2_2") (pintype "passive"))
      (node (ref "U2") (pin "A4") (pinfunction "WAKEUP0_A4") (pintype "passive"))
    )
    (net (code "29") (name "Net-(U2E-XTAL1)") (class "Default")
      (node (ref "C32") (pin "2") (pinfunction "2_2") (pintype "passive"))
      (node (ref "U2") (pin "B1") (pinfunction "XTAL1_B1") (pintype "passive"))
      (node (ref "Y1") (pin "1") (pinfunction "OSC1_1") (pintype "passive"))
    )
    (net (code "30") (name "Net-(U2E-XTAL2)") (class "Default")
      (node (ref "C33") (pin "1") (pinfunction "1_1") (pintype "passive"))
      (node (ref "U2") (pin "C1") (pinfunction "XTAL2_C1") (pintype "passive"))
      (node (ref "Y1") (pin "2") (pintype "passive"))
    )
    (net (code "31") (name "Net-(U8-VOUT)") (class "Default")
      (node (ref "C44") (pin "1") (pinfunction "1_1") (pintype "passive"))
      (node (ref "R35") (pin "2") (pinfunction "2_2") (pintype "passive"))
      (node (ref "U8") (pin "3") (pinfunction "VOUT_3") (pintype "passive"))
    )
    (net (code "32") (name "Net-(U9-VOUT)") (class "Default")
      (node (ref "C49") (pin "1") (pinfunction "1_1") (pintype "passive"))
      (node (ref "R38") (pin "2") (pinfunction "2_2") (pintype "passive"))
      (node (ref "U9") (pin "3") (pinfunction "VOUT_3") (pintype "passive"))
    )
    (net (code "33") (name "Net-(U10-CE)") (class "Default")
      (node (ref "R41") (pin "2") (pinfunction "2_2") (pintype "passive"))
      (node (ref "U10") (pin "3") (pinfunction "CE_3") (pintype "passive"))
    )
    (net (code "34") (name "Net-(U10-VOUT)") (class "Default")
      (node (ref "R40") (pin "2") (pinfunction "2_2") (pintype "passive"))
      (node (ref "U10") (pin "5") (pinfunction "VOUT_5") (pintype "passive"))
    )
    (net (code "35") (name "USB_FS_VBUS_TRGT") (class "Default")
      (node (ref "D3") (pin "2") (pinfunction "A2_2") (pintype "passive"))
      (node (ref "TP6") (pin "1") (pinfunction "TP_1") (pintype "passive"))
    )
    (net (code "36") (name "USB_HS_VBUS_TRGT") (class "Default")
      (node (ref "D4") (pin "2") (pinfunction "A2_2") (pintype "passive"))
      (node (ref "TP8") (pin "1") (pinfunction "TP_1") (pintype "passive"))
    )
    (net (code "37") (name "VDD_TARGET") (class "Default")
      (node (ref "P4") (pin "2") (pinfunction "2_2") (pintype "passive"))
      (node (ref "R37") (pin "2") (pinfunction "2_2") (pintype "passive"))
    )
    (net (code "38") (name "VDD_TARGET_1.8") (class "Default")
      (node (ref "C45") (pin "2") (pinfunction "2_2") (pintype "passive"))
      (node (ref "C46") (pin "2") (pinfunction "2_2") (pintype "passive"))
      (node (ref "P4") (pin "1") (pinfunction "1_1") (pintype "passive"))
      (node (ref "R35") (pin "1") (pinfunction "1_1") (pintype "passive"))
      (node (ref "TP5") (pin "1") (pinfunction "TP_1") (pintype "passive"))
    )
    (net (code "39") (name "VDD_TARGET_3.3") (class "Default")
      (node (ref "C50") (pin "2") (pinfunction "2_2") (pintype "passive"))
      (node (ref "C51") (pin "2") (pinfunction "2_2") (pintype "passive"))
      (node (ref "P4") (pin "3") (pinfunction "3_3") (pintype "passive"))
      (node (ref "R38") (pin "1") (pinfunction "1_1") (pintype "passive"))
      (node (ref "TP18") (pin "1") (pinfunction "TP_1") (pintype "passive"))
    )
    (net (code "40") (name "unconnected-(P5-D+-Pad3)") (class "Default")
      (node (ref "P5") (pin "3") (pinfunction "D+_3") (pintype "passive"))
    )
    (net (code "41") (name "unconnected-(P5-D--Pad2)") (class "Default")
      (node (ref "P5") (pin "2") (pinfunction "D-_2") (pintype "passive"))
    )
    (net (code "42") (name "unconnected-(P5-ID-Pad4)") (class "Default")
      (node (ref "P5") (pin "4") (pinfunction "ID_4") (pintype "passive"))
    )
    (net (code "43") (name "unconnected-(P22-Pad7)") (class "Default")
      (node (ref "P22") (pin "7") (pinfunction "7_7") (pintype "passive"))
    )
    (net (code "44") (name "unconnected-(U2D-CLK0{slash}EMC_CLK0{slash}CLKOUT{slash}SD_CLK{slash}EMC_CLK01{slash}SSP1_SCK{slash}ENET_TX_CLK_(ENET_REF_CLK)-PadK3)") (class "Default")
      (node (ref "U2") (pin "K3") (pinfunction "CLK0/EMC_CLK0/CLKOUT/SD_CLK/EMC_CLK01/SSP1_SCK/ENET_TX_CLK_(ENET_REF_CLK)_K3") (pintype "passive"))
    )
    (net (code "45") (name "unconnected-(U2D-CLK2{slash}EMC_CLK3{slash}CLKOUT{slash}SD_CLK{slash}EMC_CLK23{slash}I2S0_TX_MCLK{slash}I2S1_RX_SCK-PadK6)") (class "Default")
      (node (ref "U2") (pin "K6") (pinfunction "CLK2/EMC_CLK3/CLKOUT/SD_CLK/EMC_CLK23/I2S0_TX_MCLK/I2S1_RX_SCK_K6") (pintype "passive"))
    )
    (net (code "46") (name "unconnected-(U2D-USB1_DM-PadE10)") (class "Default")
      (node (ref "U2") (pin "E10") (pinfunction "USB1_DM_E10") (pintype "passive"))
    )
    (net (code "47") (name "unconnected-(U2D-USB1_DP-PadE9)") (class "Default")
      (node (ref "U2") (pin "E9") (pinfunction "USB1_DP_E9") (pintype "passive"))
    )
    (net (code "48") (name "unconnected-(U2E-ADC0_0{slash}ADC1_0{slash}DAC-PadA2)") (class "Default")
      (node (ref "U2") (pin "A2") (pinfunction "ADC0_0/ADC1_0/DAC_A2") (pintype "passive"))
    )
    (net (code "49") (name "unconnected-(U2E-ADC0_1{slash}ADC1_1-PadA1)") (class "Default")
      (node (ref "U2") (pin "A1") (pinfunction "ADC0_1/ADC1_1_A1") (pintype "passive"))
    )
    (net (code "50") (name "unconnected-(U2E-ADC0_2{slash}ADC1_2-PadB3)") (class "Default")
      (node (ref "U2") (pin "B3") (pinfunction "ADC0_2/ADC1_2_B3") (pintype "passive"))
    )
    (net (code "51") (name "unconnected-(U2E-ADC0_3{slash}ADC1_3-PadA3)") (class "Default")
      (node (ref "U2") (pin "A3") (pinfunction "ADC0_3/ADC1_3_A3") (pintype "passive"))
    )
    (net (code "52") (name "unconnected-(U2E-RTCX1-PadA5)") (class "Default")
      (node (ref "U2") (pin "A5") (pinfunction "RTCX1_A5") (pintype "passive"))
    )
    (net (code "53") (name "unconnected-(U2E-RTCX2-PadB5)") (class "Default")
      (node (ref "U2") (pin "B5") (pinfunction "RTCX2_B5") (pintype "passive"))
    )
    (net (code "54") (name "unconnected-(U2E-RTC_ALARM-PadC3)") (class "Default")
      (node (ref "U2") (pin "C3") (pinfunction "RTC_ALARM_C3") (pintype "passive"))
    )
    (net (code "55") (name "unconnected-(U10-NC-Pad4)") (class "Default")
      (node (ref "U10") (pin "4") (pinfunction "NC_4") (pintype "passive"))
    )
  )
)
